# ft2_redraw.net
KiCad netlist of a schematic drawn in EAGLE
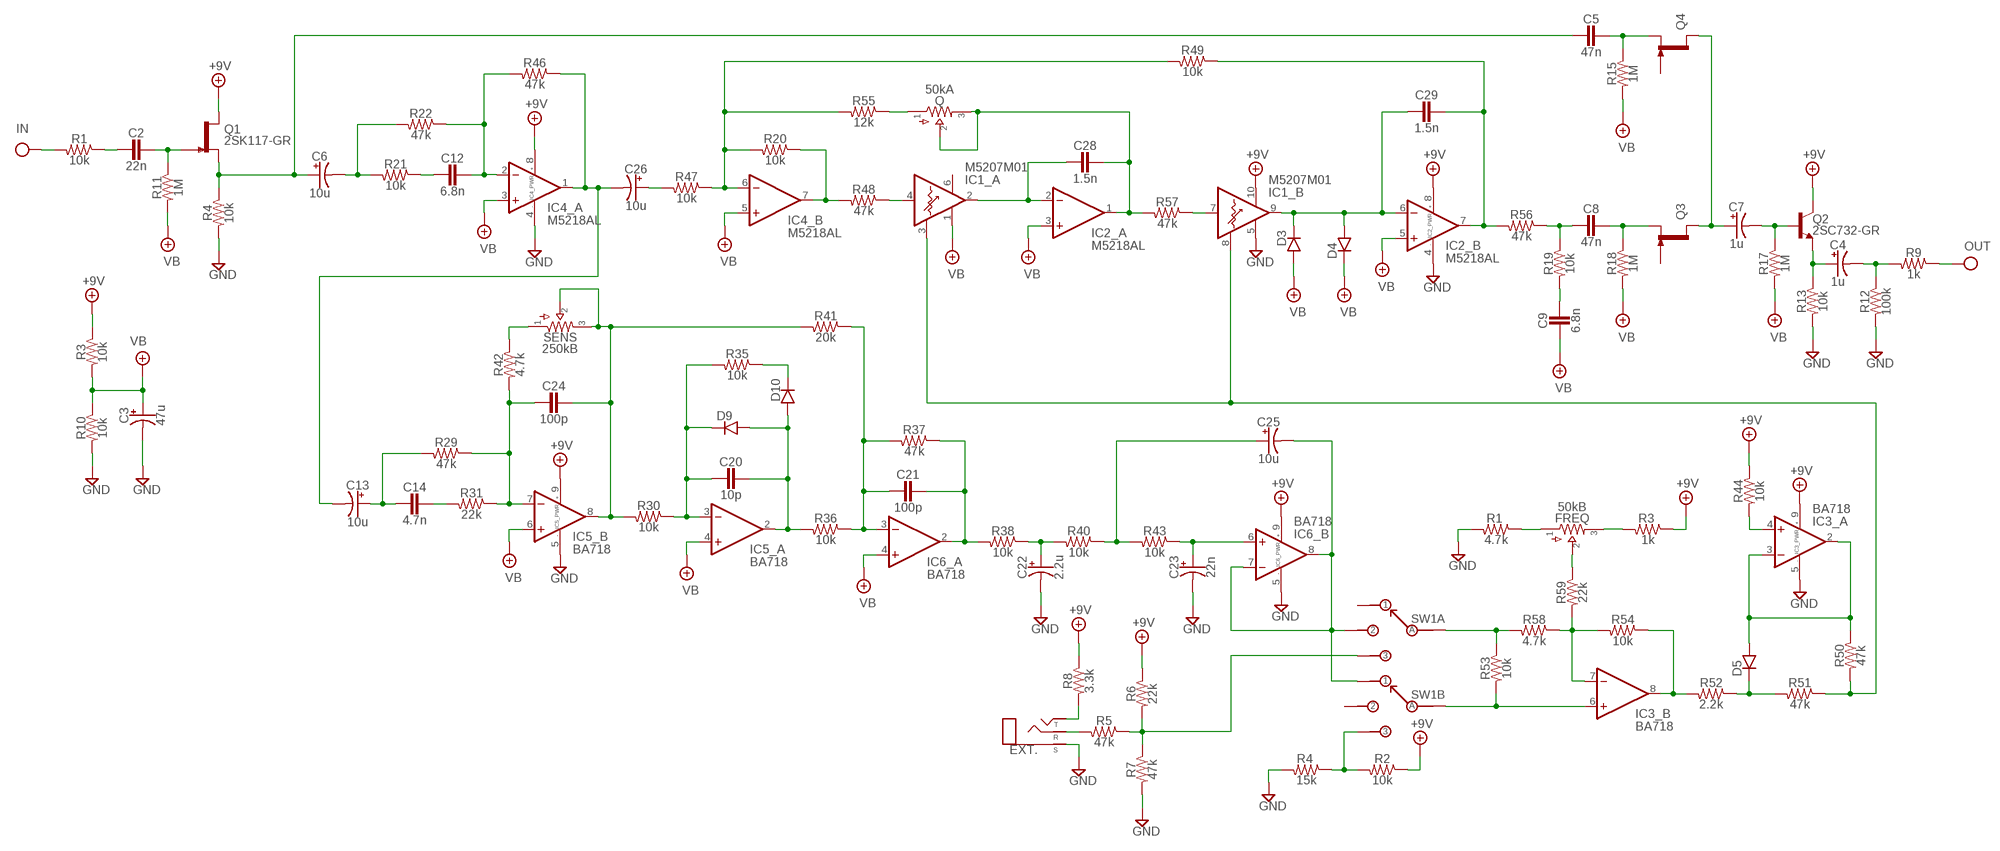
[diagram p0: schematic, sheet 1]

(export (version "E")
  (design (tool "Eeschema 10.0.6"))
  (components
    (comp (ref "C2")
      (value "22n")
      (footprint "eagle-import:BOX_SMALL")
      (libsource (lib "eagle-import") (part "CER/FILMBOX.1"))
    )
    (comp (ref "C3")
      (value "47u")
      (footprint "eagle-import:040_020")
      (libsource (lib "eagle-import") (part "0400"))
    )
    (comp (ref "C4")
      (value "1u")
      (footprint "eagle-import:040_020")
      (libsource (lib "eagle-import") (part "0400"))
    )
    (comp (ref "C5")
      (value "47n")
      (footprint "eagle-import:BOX_SMALL")
      (libsource (lib "eagle-import") (part "CER/FILMBOX.1"))
    )
    (comp (ref "C6")
      (value "10u")
      (footprint "eagle-import:040_020")
      (libsource (lib "eagle-import") (part "0400"))
    )
    (comp (ref "C7")
      (value "1u")
      (footprint "eagle-import:040_020")
      (libsource (lib "eagle-import") (part "0400"))
    )
    (comp (ref "C8")
      (value "47n")
      (footprint "eagle-import:BOX_SMALL")
      (libsource (lib "eagle-import") (part "CER/FILMBOX.1"))
    )
    (comp (ref "C9")
      (value "6.8n")
      (footprint "eagle-import:BOX_SMALL")
      (libsource (lib "eagle-import") (part "CER/FILMBOX.1"))
    )
    (comp (ref "C12")
      (value "6.8n")
      (footprint "eagle-import:BOX_SMALL")
      (libsource (lib "eagle-import") (part "CER/FILMBOX.1"))
    )
    (comp (ref "C13")
      (value "10u")
      (footprint "eagle-import:040_020")
      (libsource (lib "eagle-import") (part "0400"))
    )
    (comp (ref "C14")
      (value "4.7n")
      (footprint "eagle-import:BOX_SMALL")
      (libsource (lib "eagle-import") (part "CER/FILMBOX.1"))
    )
    (comp (ref "C20")
      (value "10p")
      (footprint "eagle-import:BOX_SMALL")
      (libsource (lib "eagle-import") (part "CER/FILMBOX.1"))
    )
    (comp (ref "C21")
      (value "100p")
      (footprint "eagle-import:BOX_SMALL")
      (libsource (lib "eagle-import") (part "CER/FILMBOX.1"))
    )
    (comp (ref "C22")
      (value "2.2u")
      (footprint "eagle-import:040_020")
      (libsource (lib "eagle-import") (part "0400"))
    )
    (comp (ref "C23")
      (value "22n")
      (footprint "eagle-import:040_020")
      (libsource (lib "eagle-import") (part "0400"))
    )
    (comp (ref "C24")
      (value "100p")
      (footprint "eagle-import:BOX_SMALL")
      (libsource (lib "eagle-import") (part "CER/FILMBOX.1"))
    )
    (comp (ref "C25")
      (value "10u")
      (footprint "eagle-import:040_020")
      (libsource (lib "eagle-import") (part "0400"))
    )
    (comp (ref "C26")
      (value "10u")
      (footprint "eagle-import:040_020")
      (libsource (lib "eagle-import") (part "0400"))
    )
    (comp (ref "C28")
      (value "1.5n")
      (footprint "eagle-import:BOX_SMALL")
      (libsource (lib "eagle-import") (part "CER/FILMBOX.1"))
    )
    (comp (ref "C29")
      (value "1.5n")
      (footprint "eagle-import:BOX_SMALL")
      (libsource (lib "eagle-import") (part "CER/FILMBOX.1"))
    )
    (comp (ref "D3")
      (value "DO35.2")
      (footprint "eagle-import:DO35-2")
      (libsource (lib "eagle-import") (part "DO35.2"))
    )
    (comp (ref "D4")
      (value "DO35.2")
      (footprint "eagle-import:DO35-2")
      (libsource (lib "eagle-import") (part "DO35.2"))
    )
    (comp (ref "D5")
      (value "DO35.2")
      (footprint "eagle-import:DO35-2")
      (libsource (lib "eagle-import") (part "DO35.2"))
    )
    (comp (ref "D9")
      (value "DO35.2")
      (footprint "eagle-import:DO35-2")
      (libsource (lib "eagle-import") (part "DO35.2"))
    )
    (comp (ref "D10")
      (value "DO35.2")
      (footprint "eagle-import:DO35-2")
      (libsource (lib "eagle-import") (part "DO35.2"))
    )
    (comp (ref "EXT.")
      (value "STEREO")
      (footprint "eagle-import:STEREO_PCB")
      (libsource (lib "eagle-import") (part "STEREO"))
    )
    (comp (ref "FREQ")
      (value "50kB")
      (footprint "eagle-import:16MM")
      (libsource (lib "eagle-import") (part "POTS16MM"))
    )
    (comp (ref "IC1")
      (value "M5207M01")
      (footprint "eagle-import:SIL10")
      (libsource (lib "eagle-import") (part "M5207L01"))
    )
    (comp (ref "IC2")
      (value "M5218AL")
      (footprint "eagle-import:DIL0")
      (libsource (lib "eagle-import") (part "DUALTH"))
    )
    (comp (ref "IC3")
      (value "BA718")
      (footprint "eagle-import:SIL09")
      (libsource (lib "eagle-import") (part "DUAL"))
    )
    (comp (ref "IC4")
      (value "M5218AL")
      (footprint "eagle-import:DIL0")
      (libsource (lib "eagle-import") (part "DUALTH"))
    )
    (comp (ref "IC5")
      (value "BA718")
      (footprint "eagle-import:SIL09")
      (libsource (lib "eagle-import") (part "DUAL"))
    )
    (comp (ref "IC6")
      (value "BA718")
      (footprint "eagle-import:SIL09")
      (libsource (lib "eagle-import") (part "DUAL"))
    )
    (comp (ref "Q")
      (value "50kA")
      (footprint "eagle-import:16MM")
      (libsource (lib "eagle-import") (part "POTS16MM"))
    )
    (comp (ref "Q1")
      (value "2SK117-GR")
      (footprint "eagle-import:TO92-")
      (libsource (lib "eagle-import") (part "2N5457"))
    )
    (comp (ref "Q2")
      (value "2SC732-GR")
      (footprint "eagle-import:TO92-")
      (libsource (lib "eagle-import") (part "2N3904"))
    )
    (comp (ref "Q3")
      (value "2N3819TO-92S")
      (footprint "eagle-import:TO92-")
      (libsource (lib "eagle-import") (part "2N3819TO-92S"))
    )
    (comp (ref "Q4")
      (value "2N3819TO-92S")
      (footprint "eagle-import:TO92-")
      (libsource (lib "eagle-import") (part "2N3819TO-92S"))
    )
    (comp (ref "R1")
      (value "10k")
      (footprint "eagle-import:R0207_3")
      (libsource (lib "eagle-import") (part "R_.3B"))
    )
    (comp (ref "R1 ")
      (value "4.7k")
      (footprint "eagle-import:R0207_3")
      (libsource (lib "eagle-import") (part "R_.3B"))
    )
    (comp (ref "R2")
      (value "10k")
      (footprint "eagle-import:R0207_3")
      (libsource (lib "eagle-import") (part "R_.3B"))
    )
    (comp (ref "R3")
      (value "10k")
      (footprint "eagle-import:R0207_3")
      (libsource (lib "eagle-import") (part "R_.3B"))
    )
    (comp (ref "R3 ")
      (value "1k")
      (footprint "eagle-import:R0207_3")
      (libsource (lib "eagle-import") (part "R_.3B"))
    )
    (comp (ref "R4")
      (value "10k")
      (footprint "eagle-import:R0207_3")
      (libsource (lib "eagle-import") (part "R_.3B"))
    )
    (comp (ref "R4 ")
      (value "15k")
      (footprint "eagle-import:R0207_3")
      (libsource (lib "eagle-import") (part "R_.3B"))
    )
    (comp (ref "R5")
      (value "47k")
      (footprint "eagle-import:R0207_3")
      (libsource (lib "eagle-import") (part "R_.3B"))
    )
    (comp (ref "R6")
      (value "22k")
      (footprint "eagle-import:R0207_3")
      (libsource (lib "eagle-import") (part "R_.3B"))
    )
    (comp (ref "R7")
      (value "47k")
      (footprint "eagle-import:R0207_3")
      (libsource (lib "eagle-import") (part "R_.3B"))
    )
    (comp (ref "R8")
      (value "3.3k")
      (footprint "eagle-import:R0207_3")
      (libsource (lib "eagle-import") (part "R_.3B"))
    )
    (comp (ref "R9")
      (value "1k")
      (footprint "eagle-import:R0207_3")
      (libsource (lib "eagle-import") (part "R_.3B"))
    )
    (comp (ref "R10")
      (value "10k")
      (footprint "eagle-import:R0207_3")
      (libsource (lib "eagle-import") (part "R_.3B"))
    )
    (comp (ref "R11")
      (value "1M")
      (footprint "eagle-import:R0207_3")
      (libsource (lib "eagle-import") (part "R_.3B"))
    )
    (comp (ref "R12")
      (value "100k")
      (footprint "eagle-import:R0207_3")
      (libsource (lib "eagle-import") (part "R_.3B"))
    )
    (comp (ref "R13")
      (value "10k")
      (footprint "eagle-import:R0207_3")
      (libsource (lib "eagle-import") (part "R_.3B"))
    )
    (comp (ref "R15")
      (value "1M")
      (footprint "eagle-import:R0207_3")
      (libsource (lib "eagle-import") (part "R_.3B"))
    )
    (comp (ref "R17")
      (value "1M")
      (footprint "eagle-import:R0207_3")
      (libsource (lib "eagle-import") (part "R_.3B"))
    )
    (comp (ref "R18")
      (value "1M")
      (footprint "eagle-import:R0207_3")
      (libsource (lib "eagle-import") (part "R_.3B"))
    )
    (comp (ref "R19")
      (value "10k")
      (footprint "eagle-import:R0207_3")
      (libsource (lib "eagle-import") (part "R_.3B"))
    )
    (comp (ref "R20")
      (value "10k")
      (footprint "eagle-import:R0207_3")
      (libsource (lib "eagle-import") (part "R_.3B"))
    )
    (comp (ref "R21")
      (value "10k")
      (footprint "eagle-import:R0207_3")
      (libsource (lib "eagle-import") (part "R_.3B"))
    )
    (comp (ref "R22")
      (value "47k")
      (footprint "eagle-import:R0207_3")
      (libsource (lib "eagle-import") (part "R_.3B"))
    )
    (comp (ref "R29")
      (value "47k")
      (footprint "eagle-import:R0207_3")
      (libsource (lib "eagle-import") (part "R_.3B"))
    )
    (comp (ref "R30")
      (value "10k")
      (footprint "eagle-import:R0207_3")
      (libsource (lib "eagle-import") (part "R_.3B"))
    )
    (comp (ref "R31")
      (value "22k")
      (footprint "eagle-import:R0207_3")
      (libsource (lib "eagle-import") (part "R_.3B"))
    )
    (comp (ref "R35")
      (value "10k")
      (footprint "eagle-import:R0207_3")
      (libsource (lib "eagle-import") (part "R_.3B"))
    )
    (comp (ref "R36")
      (value "10k")
      (footprint "eagle-import:R0207_3")
      (libsource (lib "eagle-import") (part "R_.3B"))
    )
    (comp (ref "R37")
      (value "47k")
      (footprint "eagle-import:R0207_3")
      (libsource (lib "eagle-import") (part "R_.3B"))
    )
    (comp (ref "R38")
      (value "10k")
      (footprint "eagle-import:R0207_3")
      (libsource (lib "eagle-import") (part "R_.3B"))
    )
    (comp (ref "R40")
      (value "10k")
      (footprint "eagle-import:R0207_3")
      (libsource (lib "eagle-import") (part "R_.3B"))
    )
    (comp (ref "R41")
      (value "20k")
      (footprint "eagle-import:R0207_3")
      (libsource (lib "eagle-import") (part "R_.3B"))
    )
    (comp (ref "R42")
      (value "4.7k")
      (footprint "eagle-import:R0207_3")
      (libsource (lib "eagle-import") (part "R_.3B"))
    )
    (comp (ref "R43")
      (value "10k")
      (footprint "eagle-import:R0207_3")
      (libsource (lib "eagle-import") (part "R_.3B"))
    )
    (comp (ref "R44")
      (value "10k")
      (footprint "eagle-import:R0207_3")
      (libsource (lib "eagle-import") (part "R_.3B"))
    )
    (comp (ref "R46")
      (value "47k")
      (footprint "eagle-import:R0207_3")
      (libsource (lib "eagle-import") (part "R_.3B"))
    )
    (comp (ref "R47")
      (value "10k")
      (footprint "eagle-import:R0207_3")
      (libsource (lib "eagle-import") (part "R_.3B"))
    )
    (comp (ref "R48")
      (value "47k")
      (footprint "eagle-import:R0207_3")
      (libsource (lib "eagle-import") (part "R_.3B"))
    )
    (comp (ref "R49")
      (value "10k")
      (footprint "eagle-import:R0207_3")
      (libsource (lib "eagle-import") (part "R_.3B"))
    )
    (comp (ref "R50")
      (value "47k")
      (footprint "eagle-import:R0207_3")
      (libsource (lib "eagle-import") (part "R_.3B"))
    )
    (comp (ref "R51")
      (value "47k")
      (footprint "eagle-import:R0207_3")
      (libsource (lib "eagle-import") (part "R_.3B"))
    )
    (comp (ref "R52")
      (value "2.2k")
      (footprint "eagle-import:R0207_3")
      (libsource (lib "eagle-import") (part "R_.3B"))
    )
    (comp (ref "R53")
      (value "10k")
      (footprint "eagle-import:R0207_3")
      (libsource (lib "eagle-import") (part "R_.3B"))
    )
    (comp (ref "R54")
      (value "10k")
      (footprint "eagle-import:R0207_3")
      (libsource (lib "eagle-import") (part "R_.3B"))
    )
    (comp (ref "R55")
      (value "12k")
      (footprint "eagle-import:R0207_3")
      (libsource (lib "eagle-import") (part "R_.3B"))
    )
    (comp (ref "R56")
      (value "47k")
      (footprint "eagle-import:R0207_3")
      (libsource (lib "eagle-import") (part "R_.3B"))
    )
    (comp (ref "R57")
      (value "47k")
      (footprint "eagle-import:R0207_3")
      (libsource (lib "eagle-import") (part "R_.3B"))
    )
    (comp (ref "R58")
      (value "4.7k")
      (footprint "eagle-import:R0207_3")
      (libsource (lib "eagle-import") (part "R_.3B"))
    )
    (comp (ref "R59")
      (value "22k")
      (footprint "eagle-import:R0207_3")
      (libsource (lib "eagle-import") (part "R_.3B"))
    )
    (comp (ref "SENS")
      (value "250kB")
      (footprint "eagle-import:16MM")
      (libsource (lib "eagle-import") (part "POTS16MM"))
    )
    (comp (ref "SW1A")
      (value "1P3T")
      (footprint "eagle-import:1P3T")
      (libsource (lib "eagle-import") (part "1P3T"))
    )
    (comp (ref "SW1B")
      (value "1P3T")
      (footprint "eagle-import:1P3T")
      (libsource (lib "eagle-import") (part "1P3T"))
    )
  )
  (nets
    (net (code "1") (name "+9V") (class "Default")
      (node (ref "IC1") (pin "10") (pinfunction "+PWR_10") (pintype "power_in"))
      (node (ref "IC2") (pin "8") (pinfunction "V+_8") (pintype "power_in"))
      (node (ref "IC3") (pin "9") (pinfunction "V+_9") (pintype "power_in"))
      (node (ref "IC4") (pin "8") (pinfunction "V+_8") (pintype "power_in"))
      (node (ref "IC5") (pin "9") (pinfunction "V+_9") (pintype "power_in"))
      (node (ref "IC6") (pin "9") (pinfunction "V+_9") (pintype "power_in"))
      (node (ref "Q1") (pin "3") (pinfunction "D_3") (pintype "passive"))
      (node (ref "Q2") (pin "1") (pinfunction "C_1") (pintype "passive"))
      (node (ref "R2") (pin "1") (pinfunction "1_1") (pintype "passive"))
      (node (ref "R3") (pin "1") (pinfunction "1_1") (pintype "passive"))
      (node (ref "R3 ") (pin "1") (pinfunction "1_1") (pintype "passive"))
      (node (ref "R44") (pin "1") (pinfunction "1_1") (pintype "passive"))
      (node (ref "R6") (pin "1") (pinfunction "1_1") (pintype "passive"))
      (node (ref "R8") (pin "1") (pinfunction "1_1") (pintype "passive"))
    )
    (net (code "2") (name "/+PWR") (class "Default")
      (node (ref "IC1") (pin "6") (pinfunction "+PWR_6") (pintype "power_in"))
    )
    (net (code "3") (name "GND") (class "Default")
      (node (ref "C22") (pin "-") (pinfunction "-_-") (pintype "passive"))
      (node (ref "C23") (pin "-") (pinfunction "-_-") (pintype "passive"))
      (node (ref "C3") (pin "-") (pinfunction "-_-") (pintype "passive"))
      (node (ref "EXT.") (pin "P$1") (pinfunction "S_P$1") (pintype "passive"))
      (node (ref "IC1") (pin "5") (pinfunction "-PWR_5") (pintype "power_in"))
      (node (ref "IC2") (pin "4") (pinfunction "V-_4") (pintype "power_in"))
      (node (ref "IC3") (pin "5") (pinfunction "V-_5") (pintype "power_in"))
      (node (ref "IC4") (pin "4") (pinfunction "V-_4") (pintype "power_in"))
      (node (ref "IC5") (pin "5") (pinfunction "V-_5") (pintype "power_in"))
      (node (ref "IC6") (pin "5") (pinfunction "V-_5") (pintype "power_in"))
      (node (ref "R10") (pin "2") (pinfunction "2_2") (pintype "passive"))
      (node (ref "R12") (pin "2") (pinfunction "2_2") (pintype "passive"))
      (node (ref "R13") (pin "2") (pinfunction "2_2") (pintype "passive"))
      (node (ref "R1 ") (pin "2") (pinfunction "2_2") (pintype "passive"))
      (node (ref "R4") (pin "2") (pinfunction "2_2") (pintype "passive"))
      (node (ref "R4 ") (pin "2") (pinfunction "2_2") (pintype "passive"))
      (node (ref "R7") (pin "2") (pinfunction "2_2") (pintype "passive"))
    )
    (net (code "4") (name "IN") (class "Default")
      (node (ref "R1") (pin "2") (pinfunction "2_2") (pintype "passive"))
    )
    (net (code "5") (name "Net-(C2-Pad2)") (class "Default")
      (node (ref "C2") (pin "2") (pinfunction "2_2") (pintype "passive"))
      (node (ref "R1") (pin "1") (pinfunction "1_1") (pintype "passive"))
    )
    (net (code "6") (name "Net-(C4-Pad-)") (class "Default")
      (node (ref "C4") (pin "-") (pinfunction "-_-") (pintype "passive"))
      (node (ref "R12") (pin "1") (pinfunction "1_1") (pintype "passive"))
      (node (ref "R9") (pin "2") (pinfunction "2_2") (pintype "passive"))
    )
    (net (code "7") (name "Net-(C6-Pad-)") (class "Default")
      (node (ref "C6") (pin "-") (pinfunction "-_-") (pintype "passive"))
      (node (ref "R21") (pin "2") (pinfunction "2_2") (pintype "passive"))
      (node (ref "R22") (pin "2") (pinfunction "2_2") (pintype "passive"))
    )
    (net (code "8") (name "Net-(C8-Pad2)") (class "Default")
      (node (ref "C8") (pin "2") (pinfunction "2_2") (pintype "passive"))
      (node (ref "R19") (pin "1") (pinfunction "1_1") (pintype "passive"))
      (node (ref "R56") (pin "1") (pinfunction "1_1") (pintype "passive"))
    )
    (net (code "9") (name "Net-(C9-Pad1)") (class "Default")
      (node (ref "C9") (pin "1") (pinfunction "1_1") (pintype "passive"))
      (node (ref "R19") (pin "2") (pinfunction "2_2") (pintype "passive"))
    )
    (net (code "10") (name "Net-(C12-Pad2)") (class "Default")
      (node (ref "C12") (pin "2") (pinfunction "2_2") (pintype "passive"))
      (node (ref "R21") (pin "1") (pinfunction "1_1") (pintype "passive"))
    )
    (net (code "11") (name "Net-(C13-Pad+)") (class "Default")
      (node (ref "C13") (pin "+") (pinfunction "+_+") (pintype "passive"))
      (node (ref "C14") (pin "2") (pinfunction "2_2") (pintype "passive"))
      (node (ref "R29") (pin "2") (pinfunction "2_2") (pintype "passive"))
    )
    (net (code "12") (name "Net-(C14-Pad1)") (class "Default")
      (node (ref "C14") (pin "1") (pinfunction "1_1") (pintype "passive"))
      (node (ref "R31") (pin "2") (pinfunction "2_2") (pintype "passive"))
    )
    (net (code "13") (name "Net-(C22-Pad+)") (class "Default")
      (node (ref "C22") (pin "+") (pinfunction "+_+") (pintype "passive"))
      (node (ref "R38") (pin "1") (pinfunction "1_1") (pintype "passive"))
      (node (ref "R40") (pin "2") (pinfunction "2_2") (pintype "passive"))
    )
    (net (code "14") (name "Net-(C25-Pad+)") (class "Default")
      (node (ref "C25") (pin "+") (pinfunction "+_+") (pintype "passive"))
      (node (ref "R40") (pin "1") (pinfunction "1_1") (pintype "passive"))
      (node (ref "R43") (pin "2") (pinfunction "2_2") (pintype "passive"))
    )
    (net (code "15") (name "Net-(C26-Pad+)") (class "Default")
      (node (ref "C26") (pin "+") (pinfunction "+_+") (pintype "passive"))
      (node (ref "R47") (pin "2") (pinfunction "2_2") (pintype "passive"))
    )
    (net (code "16") (name "Net-(D5-PadC)") (class "Default")
      (node (ref "D5") (pin "C") (pinfunction "C_C") (pintype "passive"))
      (node (ref "R51") (pin "2") (pinfunction "2_2") (pintype "passive"))
      (node (ref "R52") (pin "1") (pinfunction "1_1") (pintype "passive"))
    )
    (net (code "17") (name "Net-(D10-PadC)") (class "Default")
      (node (ref "D10") (pin "C") (pinfunction "C_C") (pintype "passive"))
      (node (ref "R35") (pin "1") (pinfunction "1_1") (pintype "passive"))
    )
    (net (code "18") (name "Net-(EXT.-R)") (class "Default")
      (node (ref "EXT.") (pin "P$2") (pinfunction "R_P$2") (pintype "passive"))
      (node (ref "R5") (pin "2") (pinfunction "2_2") (pintype "passive"))
    )
    (net (code "19") (name "Net-(EXT.-T)") (class "Default")
      (node (ref "EXT.") (pin "P$3") (pinfunction "T_P$3") (pintype "passive"))
      (node (ref "R8") (pin "2") (pinfunction "2_2") (pintype "passive"))
    )
    (net (code "20") (name "Net-(FREQ-Pad1)") (class "Default")
      (node (ref "FREQ") (pin "1") (pinfunction "1_1") (pintype "passive"))
      (node (ref "R1 ") (pin "1") (pinfunction "1_1") (pintype "passive"))
    )
    (net (code "21") (name "Net-(FREQ-Pad2)") (class "Default")
      (node (ref "FREQ") (pin "2") (pinfunction "2_2") (pintype "passive"))
      (node (ref "R59") (pin "1") (pinfunction "1_1") (pintype "passive"))
    )
    (net (code "22") (name "Net-(FREQ-Pad3)") (class "Default")
      (node (ref "FREQ") (pin "3") (pinfunction "3_3") (pintype "passive"))
      (node (ref "R3 ") (pin "2") (pinfunction "2_2") (pintype "passive"))
    )
    (net (code "23") (name "Net-(IC1A-IN)") (class "Default")
      (node (ref "IC1") (pin "4") (pinfunction "IN_4") (pintype "input"))
      (node (ref "R48") (pin "1") (pinfunction "1_1") (pintype "passive"))
    )
    (net (code "24") (name "Net-(IC1A-OUT)") (class "Default")
      (node (ref "C28") (pin "2") (pinfunction "2_2") (pintype "passive"))
      (node (ref "IC1") (pin "2") (pinfunction "OUT_2") (pintype "output"))
      (node (ref "IC2") (pin "2") (pinfunction "-IN_2") (pintype "input"))
    )
    (net (code "25") (name "Net-(IC1A-VC)") (class "Default")
      (node (ref "IC1") (pin "3") (pinfunction "VC_3") (pintype "bidirectional"))
      (node (ref "IC1") (pin "8") (pinfunction "VC_8") (pintype "bidirectional"))
      (node (ref "R50") (pin "2") (pinfunction "2_2") (pintype "passive"))
      (node (ref "R51") (pin "1") (pinfunction "1_1") (pintype "passive"))
    )
    (net (code "26") (name "Net-(IC1B-IN)") (class "Default")
      (node (ref "IC1") (pin "7") (pinfunction "IN_7") (pintype "input"))
      (node (ref "R57") (pin "1") (pinfunction "1_1") (pintype "passive"))
    )
    (net (code "27") (name "Net-(IC1B-OUT)") (class "Default")
      (node (ref "C29") (pin "2") (pinfunction "2_2") (pintype "passive"))
      (node (ref "D3") (pin "C") (pinfunction "C_C") (pintype "passive"))
      (node (ref "D4") (pin "A") (pinfunction "A_A") (pintype "passive"))
      (node (ref "IC1") (pin "9") (pinfunction "OUT_9") (pintype "output"))
      (node (ref "IC2") (pin "6") (pinfunction "-IN_6") (pintype "input"))
    )
    (net (code "28") (name "Net-(IC2A-OUT)") (class "Default")
      (node (ref "C28") (pin "1") (pinfunction "1_1") (pintype "passive"))
      (node (ref "IC2") (pin "1") (pinfunction "OUT_1") (pintype "output"))
      (node (ref "Q") (pin "2") (pinfunction "2_2") (pintype "passive"))
      (node (ref "Q") (pin "3") (pinfunction "3_3") (pintype "passive"))
      (node (ref "R57") (pin "2") (pinfunction "2_2") (pintype "passive"))
    )
    (net (code "29") (name "Net-(IC2B-OUT)") (class "Default")
      (node (ref "C29") (pin "1") (pinfunction "1_1") (pintype "passive"))
      (node (ref "IC2") (pin "7") (pinfunction "OUT_7") (pintype "output"))
      (node (ref "R49") (pin "1") (pinfunction "1_1") (pintype "passive"))
      (node (ref "R56") (pin "2") (pinfunction "2_2") (pintype "passive"))
    )
    (net (code "30") (name "Net-(IC3A-+IN)") (class "Default")
      (node (ref "IC3") (pin "4") (pinfunction "+IN_4") (pintype "input"))
      (node (ref "R44") (pin "2") (pinfunction "2_2") (pintype "passive"))
    )
    (net (code "31") (name "Net-(IC3A--IN)") (class "Default")
      (node (ref "D5") (pin "A") (pinfunction "A_A") (pintype "passive"))
      (node (ref "IC3") (pin "2") (pinfunction "OUT_2") (pintype "output"))
      (node (ref "IC3") (pin "3") (pinfunction "-IN_3") (pintype "input"))
      (node (ref "R50") (pin "1") (pinfunction "1_1") (pintype "passive"))
    )
    (net (code "32") (name "Net-(IC3B-+IN)") (class "Default")
      (node (ref "IC3") (pin "6") (pinfunction "+IN_6") (pintype "input"))
      (node (ref "R53") (pin "2") (pinfunction "2_2") (pintype "passive"))
      (node (ref "SW1B") (pin "P$1") (pinfunction "A_P$1") (pintype "bidirectional"))
    )
    (net (code "33") (name "Net-(IC3B--IN)") (class "Default")
      (node (ref "IC3") (pin "7") (pinfunction "-IN_7") (pintype "input"))
      (node (ref "R54") (pin "2") (pinfunction "2_2") (pintype "passive"))
      (node (ref "R58") (pin "1") (pinfunction "1_1") (pintype "passive"))
      (node (ref "R59") (pin "2") (pinfunction "2_2") (pintype "passive"))
    )
    (net (code "34") (name "Net-(IC3B-OUT)") (class "Default")
      (node (ref "IC3") (pin "8") (pinfunction "OUT_8") (pintype "output"))
      (node (ref "R52") (pin "2") (pinfunction "2_2") (pintype "passive"))
      (node (ref "R54") (pin "1") (pinfunction "1_1") (pintype "passive"))
    )
    (net (code "35") (name "Net-(IC4A--IN)") (class "Default")
      (node (ref "C12") (pin "1") (pinfunction "1_1") (pintype "passive"))
      (node (ref "IC4") (pin "2") (pinfunction "-IN_2") (pintype "input"))
      (node (ref "R22") (pin "1") (pinfunction "1_1") (pintype "passive"))
      (node (ref "R46") (pin "2") (pinfunction "2_2") (pintype "passive"))
    )
    (net (code "36") (name "Net-(IC4A-OUT)") (class "Default")
      (node (ref "C13") (pin "-") (pinfunction "-_-") (pintype "passive"))
      (node (ref "C26") (pin "-") (pinfunction "-_-") (pintype "passive"))
      (node (ref "IC4") (pin "1") (pinfunction "OUT_1") (pintype "output"))
      (node (ref "R46") (pin "1") (pinfunction "1_1") (pintype "passive"))
    )
    (net (code "37") (name "Net-(IC4B--IN)") (class "Default")
      (node (ref "IC4") (pin "6") (pinfunction "-IN_6") (pintype "input"))
      (node (ref "R20") (pin "2") (pinfunction "2_2") (pintype "passive"))
      (node (ref "R47") (pin "1") (pinfunction "1_1") (pintype "passive"))
      (node (ref "R49") (pin "2") (pinfunction "2_2") (pintype "passive"))
      (node (ref "R55") (pin "2") (pinfunction "2_2") (pintype "passive"))
    )
    (net (code "38") (name "Net-(IC4B-OUT)") (class "Default")
      (node (ref "IC4") (pin "7") (pinfunction "OUT_7") (pintype "output"))
      (node (ref "R20") (pin "1") (pinfunction "1_1") (pintype "passive"))
      (node (ref "R48") (pin "2") (pinfunction "2_2") (pintype "passive"))
    )
    (net (code "39") (name "Net-(IC5A--IN)") (class "Default")
      (node (ref "C20") (pin "2") (pinfunction "2_2") (pintype "passive"))
      (node (ref "D9") (pin "C") (pinfunction "C_C") (pintype "passive"))
      (node (ref "IC5") (pin "3") (pinfunction "-IN_3") (pintype "input"))
      (node (ref "R30") (pin "1") (pinfunction "1_1") (pintype "passive"))
      (node (ref "R35") (pin "2") (pinfunction "2_2") (pintype "passive"))
    )
    (net (code "40") (name "Net-(IC5A-OUT)") (class "Default")
      (node (ref "C20") (pin "1") (pinfunction "1_1") (pintype "passive"))
      (node (ref "D10") (pin "A") (pinfunction "A_A") (pintype "passive"))
      (node (ref "D9") (pin "A") (pinfunction "A_A") (pintype "passive"))
      (node (ref "IC5") (pin "2") (pinfunction "OUT_2") (pintype "output"))
      (node (ref "R36") (pin "2") (pinfunction "2_2") (pintype "passive"))
    )
    (net (code "41") (name "Net-(IC5B--IN)") (class "Default")
      (node (ref "C24") (pin "2") (pinfunction "2_2") (pintype "passive"))
      (node (ref "IC5") (pin "7") (pinfunction "-IN_7") (pintype "input"))
      (node (ref "R29") (pin "1") (pinfunction "1_1") (pintype "passive"))
      (node (ref "R31") (pin "1") (pinfunction "1_1") (pintype "passive"))
      (node (ref "R42") (pin "2") (pinfunction "2_2") (pintype "passive"))
    )
    (net (code "42") (name "Net-(IC5B-OUT)") (class "Default")
      (node (ref "C24") (pin "1") (pinfunction "1_1") (pintype "passive"))
      (node (ref "IC5") (pin "8") (pinfunction "OUT_8") (pintype "output"))
      (node (ref "R30") (pin "2") (pinfunction "2_2") (pintype "passive"))
      (node (ref "R41") (pin "2") (pinfunction "2_2") (pintype "passive"))
      (node (ref "SENS") (pin "2") (pinfunction "2_2") (pintype "passive"))
      (node (ref "SENS") (pin "3") (pinfunction "3_3") (pintype "passive"))
    )
    (net (code "43") (name "Net-(IC6A--IN)") (class "Default")
      (node (ref "C21") (pin "2") (pinfunction "2_2") (pintype "passive"))
      (node (ref "IC6") (pin "3") (pinfunction "-IN_3") (pintype "input"))
      (node (ref "R36") (pin "1") (pinfunction "1_1") (pintype "passive"))
      (node (ref "R37") (pin "2") (pinfunction "2_2") (pintype "passive"))
      (node (ref "R41") (pin "1") (pinfunction "1_1") (pintype "passive"))
    )
    (net (code "44") (name "Net-(IC6A-OUT)") (class "Default")
      (node (ref "C21") (pin "1") (pinfunction "1_1") (pintype "passive"))
      (node (ref "IC6") (pin "2") (pinfunction "OUT_2") (pintype "output"))
      (node (ref "R37") (pin "1") (pinfunction "1_1") (pintype "passive"))
      (node (ref "R38") (pin "2") (pinfunction "2_2") (pintype "passive"))
    )
    (net (code "45") (name "Net-(IC6B-+IN)") (class "Default")
      (node (ref "C23") (pin "+") (pinfunction "+_+") (pintype "passive"))
      (node (ref "IC6") (pin "6") (pinfunction "+IN_6") (pintype "input"))
      (node (ref "R43") (pin "1") (pinfunction "1_1") (pintype "passive"))
    )
    (net (code "46") (name "Net-(IC6B--IN)") (class "Default")
      (node (ref "C25") (pin "-") (pinfunction "-_-") (pintype "passive"))
      (node (ref "IC6") (pin "7") (pinfunction "-IN_7") (pintype "input"))
      (node (ref "IC6") (pin "8") (pinfunction "OUT_8") (pintype "output"))
      (node (ref "SW1A") (pin "P$3") (pinfunction "2_P$3") (pintype "bidirectional"))
      (node (ref "SW1B") (pin "P$2") (pinfunction "1_P$2") (pintype "bidirectional"))
    )
    (net (code "47") (name "Net-(Q-Pad1)") (class "Default")
      (node (ref "Q") (pin "1") (pinfunction "1_1") (pintype "passive"))
      (node (ref "R55") (pin "1") (pinfunction "1_1") (pintype "passive"))
    )
    (net (code "48") (name "Net-(Q1-G)") (class "Default")
      (node (ref "C2") (pin "1") (pinfunction "1_1") (pintype "passive"))
      (node (ref "Q1") (pin "1") (pinfunction "G_1") (pintype "passive"))
      (node (ref "R11") (pin "1") (pinfunction "1_1") (pintype "passive"))
    )
    (net (code "49") (name "Net-(Q1-S)") (class "Default")
      (node (ref "C5") (pin "2") (pinfunction "2_2") (pintype "passive"))
      (node (ref "C6") (pin "+") (pinfunction "+_+") (pintype "passive"))
      (node (ref "Q1") (pin "2") (pinfunction "S_2") (pintype "passive"))
      (node (ref "R4") (pin "1") (pinfunction "1_1") (pintype "passive"))
    )
    (net (code "50") (name "Net-(Q2-B)") (class "Default")
      (node (ref "C7") (pin "-") (pinfunction "-_-") (pintype "passive"))
      (node (ref "Q2") (pin "2") (pinfunction "B_2") (pintype "passive"))
      (node (ref "R17") (pin "1") (pinfunction "1_1") (pintype "passive"))
    )
    (net (code "51") (name "Net-(Q2-E)") (class "Default")
      (node (ref "C4") (pin "+") (pinfunction "+_+") (pintype "passive"))
      (node (ref "Q2") (pin "3") (pinfunction "E_3") (pintype "passive"))
      (node (ref "R13") (pin "1") (pinfunction "1_1") (pintype "passive"))
    )
    (net (code "52") (name "Net-(Q3-D)") (class "Default")
      (node (ref "C7") (pin "+") (pinfunction "+_+") (pintype "passive"))
      (node (ref "Q3") (pin "3") (pinfunction "D_3") (pintype "passive"))
      (node (ref "Q4") (pin "3") (pinfunction "D_3") (pintype "passive"))
    )
    (net (code "53") (name "Net-(Q3-S)") (class "Default")
      (node (ref "C8") (pin "1") (pinfunction "1_1") (pintype "passive"))
      (node (ref "Q3") (pin "1") (pinfunction "S_1") (pintype "passive"))
      (node (ref "R18") (pin "1") (pinfunction "1_1") (pintype "passive"))
    )
    (net (code "54") (name "Net-(Q4-S)") (class "Default")
      (node (ref "C5") (pin "1") (pinfunction "1_1") (pintype "passive"))
      (node (ref "Q4") (pin "1") (pinfunction "S_1") (pintype "passive"))
      (node (ref "R15") (pin "1") (pinfunction "1_1") (pintype "passive"))
    )
    (net (code "55") (name "Net-(R42-Pad1)") (class "Default")
      (node (ref "R42") (pin "1") (pinfunction "1_1") (pintype "passive"))
      (node (ref "SENS") (pin "1") (pinfunction "1_1") (pintype "passive"))
    )
    (net (code "56") (name "Net-(SW1A-3)") (class "Default")
      (node (ref "R5") (pin "1") (pinfunction "1_1") (pintype "passive"))
      (node (ref "R6") (pin "2") (pinfunction "2_2") (pintype "passive"))
      (node (ref "R7") (pin "1") (pinfunction "1_1") (pintype "passive"))
      (node (ref "SW1A") (pin "P$4") (pinfunction "3_P$4") (pintype "bidirectional"))
    )
    (net (code "57") (name "Net-(SW1A-A)") (class "Default")
      (node (ref "R53") (pin "1") (pinfunction "1_1") (pintype "passive"))
      (node (ref "R58") (pin "2") (pinfunction "2_2") (pintype "passive"))
      (node (ref "SW1A") (pin "P$1") (pinfunction "A_P$1") (pintype "bidirectional"))
    )
    (net (code "58") (name "Net-(SW1B-3)") (class "Default")
      (node (ref "R2") (pin "2") (pinfunction "2_2") (pintype "passive"))
      (node (ref "R4 ") (pin "1") (pinfunction "1_1") (pintype "passive"))
      (node (ref "SW1B") (pin "P$4") (pinfunction "3_P$4") (pintype "bidirectional"))
    )
    (net (code "59") (name "OUT") (class "Default")
      (node (ref "R9") (pin "1") (pinfunction "1_1") (pintype "passive"))
    )
    (net (code "60") (name "VB") (class "Default")
      (node (ref "C3") (pin "+") (pinfunction "+_+") (pintype "passive"))
      (node (ref "C9") (pin "2") (pinfunction "2_2") (pintype "passive"))
      (node (ref "D3") (pin "A") (pinfunction "A_A") (pintype "passive"))
      (node (ref "D4") (pin "C") (pinfunction "C_C") (pintype "passive"))
      (node (ref "IC1") (pin "1") (pinfunction "-PWR_1") (pintype "power_in"))
      (node (ref "IC2") (pin "3") (pinfunction "+IN_3") (pintype "input"))
      (node (ref "IC2") (pin "5") (pinfunction "+IN_5") (pintype "input"))
      (node (ref "IC4") (pin "3") (pinfunction "+IN_3") (pintype "input"))
      (node (ref "IC4") (pin "5") (pinfunction "+IN_5") (pintype "input"))
      (node (ref "IC5") (pin "4") (pinfunction "+IN_4") (pintype "input"))
      (node (ref "IC5") (pin "6") (pinfunction "+IN_6") (pintype "input"))
      (node (ref "IC6") (pin "4") (pinfunction "+IN_4") (pintype "input"))
      (node (ref "R10") (pin "1") (pinfunction "1_1") (pintype "passive"))
      (node (ref "R11") (pin "2") (pinfunction "2_2") (pintype "passive"))
      (node (ref "R15") (pin "2") (pinfunction "2_2") (pintype "passive"))
      (node (ref "R17") (pin "2") (pinfunction "2_2") (pintype "passive"))
      (node (ref "R18") (pin "2") (pinfunction "2_2") (pintype "passive"))
      (node (ref "R3") (pin "2") (pinfunction "2_2") (pintype "passive"))
    )
    (net (code "61") (name "unconnected-(Q3-G-Pad2)") (class "Default")
      (node (ref "Q3") (pin "2") (pinfunction "G_2") (pintype "passive"))
    )
    (net (code "62") (name "unconnected-(Q4-G-Pad2)") (class "Default")
      (node (ref "Q4") (pin "2") (pinfunction "G_2") (pintype "passive"))
    )
    (net (code "63") (name "unconnected-(SW1A-1-PadP$2)") (class "Default")
      (node (ref "SW1A") (pin "P$2") (pinfunction "1_P$2") (pintype "bidirectional"))
    )
    (net (code "64") (name "unconnected-(SW1B-2-PadP$3)") (class "Default")
      (node (ref "SW1B") (pin "P$3") (pinfunction "2_P$3") (pintype "bidirectional"))
    )
  )
)
